# main.net
KiCad netlist of a schematic drawn in Altium Designer
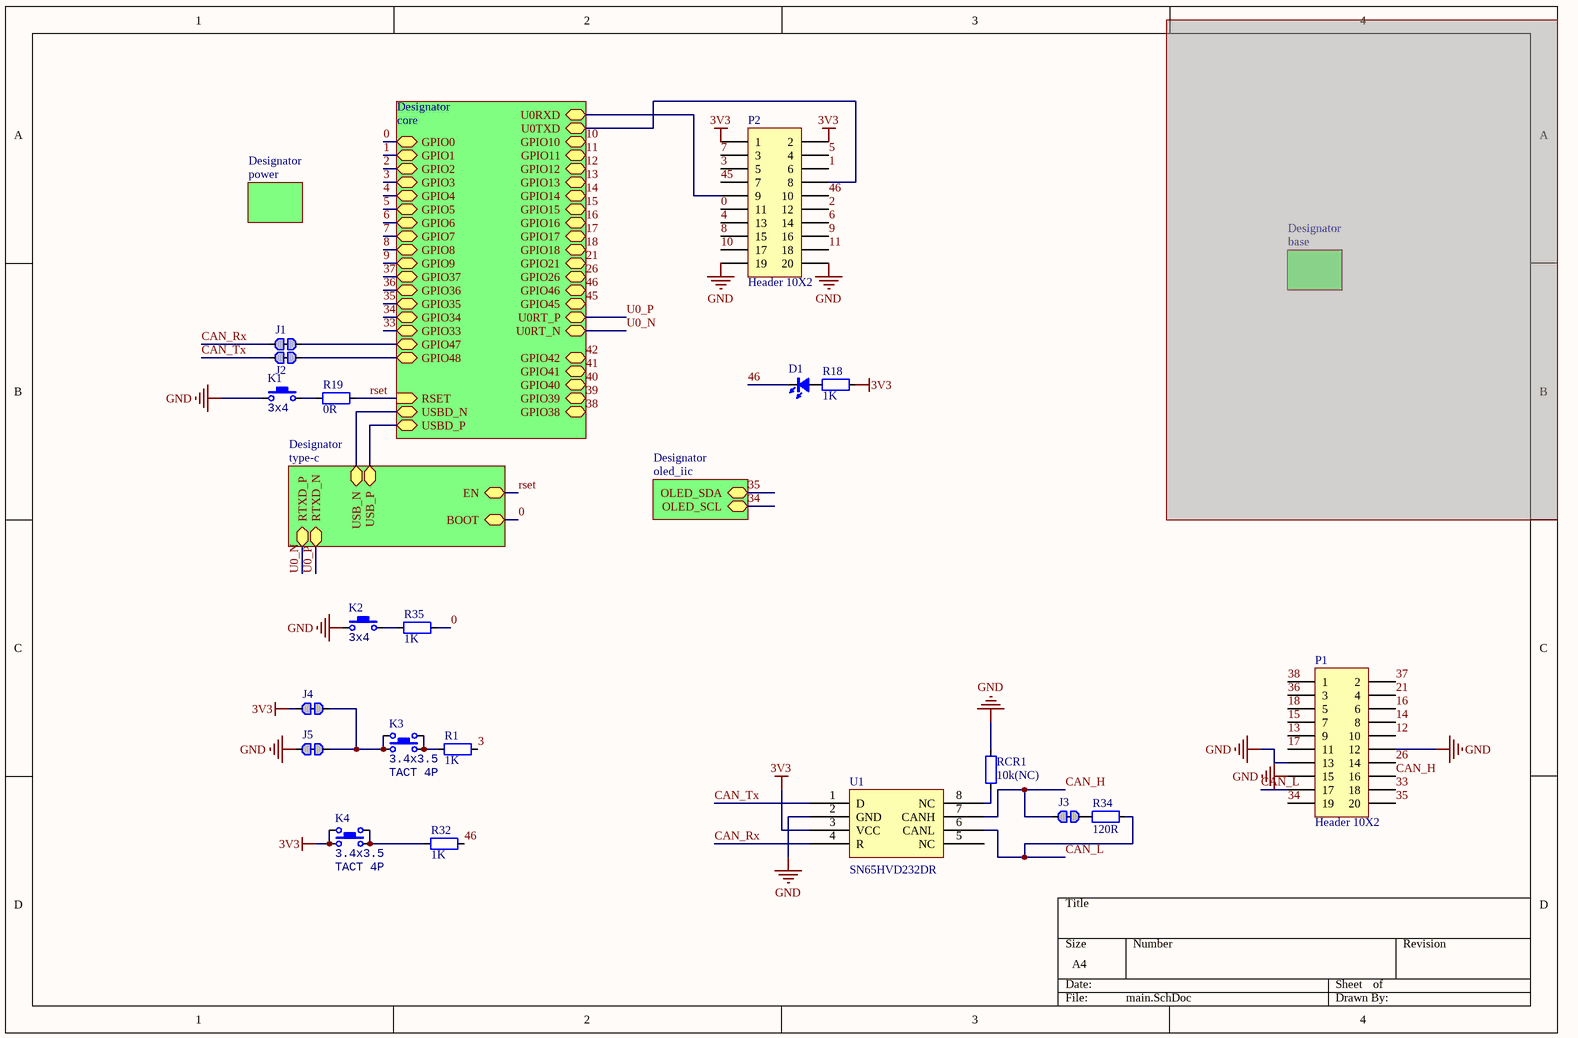
[diagram p0: main.SchDoc]

(export (version "E")
  (design (tool "Eeschema 10.0.6"))
  (components
    (comp (ref "D1")
      (value "color?")
      (footprint "LED_0402_RED")
      (description "LED")
      (libsource (lib "KitSprout") (part "LED_0402"))
    )
    (comp (ref "J1")
      (value "跳线")
      (footprint "0402-0R")
      (description "Resistor")
      (fields (field (name "PUBLISHER") "Altium Limited"))
      (libsource (lib "MyPcbLib") (part "跳线"))
    )
    (comp (ref "J2")
      (value "跳线")
      (footprint "0402-0R")
      (description "Resistor")
      (fields (field (name "PUBLISHER") "Altium Limited"))
      (libsource (lib "MyPcbLib") (part "跳线"))
    )
    (comp (ref "J3")
      (value "跳线")
      (footprint "0402-0R")
      (description "Resistor")
      (fields (field (name "PUBLISHER") "Altium Limited"))
      (libsource (lib "MyPcbLib") (part "跳线"))
    )
    (comp (ref "J4")
      (value "跳线")
      (footprint "0402-0R")
      (description "Resistor")
      (fields (field (name "PUBLISHER") "Altium Limited"))
      (libsource (lib "MyPcbLib") (part "跳线"))
    )
    (comp (ref "J5")
      (value "跳线")
      (footprint "0402-0R")
      (description "Resistor")
      (fields (field (name "PUBLISHER") "Altium Limited"))
      (libsource (lib "MyPcbLib") (part "跳线"))
    )
    (comp (ref "K1")
      (value "3x4")
      (footprint "ButtonTACT_3x4x2_180")
      (description "Button")
      (fields (field (name "Comment") "TACT 2P"))
      (libsource (lib "KitSprout") (part "ButtonTACT_3x4x2_180"))
    )
    (comp (ref "K2")
      (value "3x4")
      (footprint "ButtonTACT_3x4x2_180")
      (description "Button")
      (fields (field (name "Comment") "TACT 2P"))
      (libsource (lib "KitSprout") (part "ButtonTACT_3x4x2_180"))
    )
    (comp (ref "K3")
      (value "3.4x3.5")
      (footprint "ButtonTACT_3.5*3.55_90")
      (description "Button")
      (fields (field (name "TYPE") "TACT 4P") (field (name "Comment") "TACT 4P"))
      (libsource (lib "KitSprout") (part "ButtonTACT"))
    )
    (comp (ref "K4")
      (value "3.4x3.5")
      (footprint "ButtonTACT_3.5*3.55_90")
      (description "Button")
      (fields (field (name "TYPE") "TACT 4P") (field (name "Comment") "TACT 4P"))
      (libsource (lib "KitSprout") (part "ButtonTACT"))
    )
    (comp (ref "P1")
      (value "Header 10X2")
      (footprint "HEAER_0.8mm_2x10P_M")
      (description "Header, 10-Pin, Dual row")
      (fields (field (name "PUBLISHER") "Altium Limited"))
      (libsource (lib "Miscellaneous Connectors") (part "Header 10X2"))
    )
    (comp (ref "P2")
      (value "Header 10X2")
      (footprint "HEAER_0.8mm_2x10P_M")
      (description "Header, 10-Pin, Dual row")
      (fields (field (name "PUBLISHER") "Altium Limited"))
      (libsource (lib "Miscellaneous Connectors") (part "Header 10X2"))
    )
    (comp (ref "R1")
      (value "1K")
      (footprint "RES_0402")
      (description "Resistor")
      (libsource (lib "MyPcbLib") (part "电阻-0402"))
    )
    (comp (ref "R18")
      (value "1K")
      (footprint "RES_0402")
      (description "Resistor")
      (libsource (lib "") (part "电阻-0402_1"))
    )
    (comp (ref "R19")
      (value "0R")
      (footprint "RES_0402")
      (description "Resistor")
      (libsource (lib "MyPcbLib") (part "电阻-0402"))
    )
    (comp (ref "R32")
      (value "1K")
      (footprint "RES_0402")
      (description "Resistor")
      (libsource (lib "MyPcbLib") (part "电阻-0402"))
    )
    (comp (ref "R34")
      (value "120R")
      (footprint "RES_0402")
      (description "Resistor")
      (libsource (lib "MyPcbLib") (part "电阻-0402"))
    )
    (comp (ref "R35")
      (value "1K")
      (footprint "RES_0402")
      (description "Resistor")
      (libsource (lib "MyPcbLib") (part "电阻-0402"))
    )
    (comp (ref "RCR1")
      (value "10k(NC)")
      (footprint "RES_0402")
      (description "Resistor")
      (libsource (lib "") (part "电阻-0402_2"))
    )
    (comp (ref "U1")
      (value "SN65HVD232D")
      (footprint "SO-8")
      (fields
        (field (name "MANUFACTURER") "Texas Instruments")
        (field (name "MANUFACTURER PART NUMBER") "SN65HVD232DR")
      )
      (libsource (lib "MyPcbLib") (part "SN65HVD232D"))
    )
  )
  (nets
    (net (code "1") (name "/0") (class "Default")
      (node (ref "P2") (pin "11") (pinfunction "11_11") (pintype "passive"))
      (node (ref "R35") (pin "2") (pinfunction "2_2") (pintype "passive"))
    )
    (net (code "2") (name "/1") (class "Default")
      (node (ref "P2") (pin "6") (pinfunction "6_6") (pintype "passive"))
    )
    (net (code "3") (name "/2") (class "Default")
      (node (ref "P2") (pin "12") (pinfunction "12_12") (pintype "passive"))
    )
    (net (code "4") (name "/3") (class "Default")
      (node (ref "P2") (pin "5") (pinfunction "5_5") (pintype "passive"))
      (node (ref "R1") (pin "2") (pinfunction "2_2") (pintype "passive"))
    )
    (net (code "5") (name "/4") (class "Default")
      (node (ref "P2") (pin "13") (pinfunction "13_13") (pintype "passive"))
    )
    (net (code "6") (name "/5") (class "Default")
      (node (ref "P2") (pin "4") (pinfunction "4_4") (pintype "passive"))
    )
    (net (code "7") (name "/6") (class "Default")
      (node (ref "P2") (pin "14") (pinfunction "14_14") (pintype "passive"))
    )
    (net (code "8") (name "/7") (class "Default")
      (node (ref "P2") (pin "3") (pinfunction "3_3") (pintype "passive"))
    )
    (net (code "9") (name "/8") (class "Default")
      (node (ref "P2") (pin "15") (pinfunction "15_15") (pintype "passive"))
    )
    (net (code "10") (name "/9") (class "Default")
      (node (ref "P2") (pin "16") (pinfunction "16_16") (pintype "passive"))
    )
    (net (code "11") (name "/10") (class "Default")
      (node (ref "P2") (pin "17") (pinfunction "17_17") (pintype "passive"))
    )
    (net (code "12") (name "/11") (class "Default")
      (node (ref "P2") (pin "18") (pinfunction "18_18") (pintype "passive"))
    )
    (net (code "13") (name "/12") (class "Default")
      (node (ref "P1") (pin "10") (pinfunction "10_10") (pintype "passive"))
    )
    (net (code "14") (name "/13") (class "Default")
      (node (ref "P1") (pin "9") (pinfunction "9_9") (pintype "passive"))
    )
    (net (code "15") (name "/14") (class "Default")
      (node (ref "P1") (pin "8") (pinfunction "8_8") (pintype "passive"))
    )
    (net (code "16") (name "/15") (class "Default")
      (node (ref "P1") (pin "7") (pinfunction "7_7") (pintype "passive"))
    )
    (net (code "17") (name "/16") (class "Default")
      (node (ref "P1") (pin "6") (pinfunction "6_6") (pintype "passive"))
    )
    (net (code "18") (name "/17") (class "Default")
      (node (ref "P1") (pin "11") (pinfunction "11_11") (pintype "passive"))
    )
    (net (code "19") (name "/18") (class "Default")
      (node (ref "P1") (pin "5") (pinfunction "5_5") (pintype "passive"))
    )
    (net (code "20") (name "/21") (class "Default")
      (node (ref "P1") (pin "4") (pinfunction "4_4") (pintype "passive"))
    )
    (net (code "21") (name "/26") (class "Default")
      (node (ref "P1") (pin "14") (pinfunction "14_14") (pintype "passive"))
    )
    (net (code "22") (name "/33") (class "Default")
      (node (ref "P1") (pin "18") (pinfunction "18_18") (pintype "passive"))
    )
    (net (code "23") (name "/34") (class "Default")
      (node (ref "P1") (pin "19") (pinfunction "19_19") (pintype "passive"))
    )
    (net (code "24") (name "/35") (class "Default")
      (node (ref "P1") (pin "20") (pinfunction "20_20") (pintype "passive"))
    )
    (net (code "25") (name "/36") (class "Default")
      (node (ref "P1") (pin "3") (pinfunction "3_3") (pintype "passive"))
    )
    (net (code "26") (name "/37") (class "Default")
      (node (ref "P1") (pin "2") (pinfunction "2_2") (pintype "passive"))
    )
    (net (code "27") (name "/38") (class "Default")
      (node (ref "P1") (pin "1") (pinfunction "1_1") (pintype "passive"))
    )
    (net (code "32") (name "/45") (class "Default")
      (node (ref "P2") (pin "7") (pinfunction "7_7") (pintype "passive"))
    )
    (net (code "33") (name "/46") (class "Default")
      (node (ref "D1") (pin "2") (pinfunction "K_2") (pintype "passive"))
      (node (ref "P2") (pin "10") (pinfunction "10_10") (pintype "passive"))
      (node (ref "R32") (pin "2") (pinfunction "2_2") (pintype "passive"))
    )
    (net (code "34") (name "/CAN_H") (class "Default")
      (node (ref "J3") (pin "1") (pinfunction "1_1") (pintype "passive"))
      (node (ref "P1") (pin "16") (pinfunction "16_16") (pintype "passive"))
      (node (ref "U1") (pin "7") (pinfunction "CANH_7") (pintype "passive"))
    )
    (net (code "35") (name "/CAN_L") (class "Default")
      (node (ref "P1") (pin "17") (pinfunction "17_17") (pintype "passive"))
      (node (ref "R34") (pin "2") (pinfunction "2_2") (pintype "passive"))
      (node (ref "U1") (pin "6") (pinfunction "CANL_6") (pintype "passive"))
    )
    (net (code "36") (name "/CAN_Rx") (class "Default")
      (node (ref "J1") (pin "1") (pinfunction "1_1") (pintype "passive"))
      (node (ref "U1") (pin "4") (pinfunction "R_4") (pintype "passive"))
    )
    (net (code "37") (name "/CAN_Tx") (class "Default")
      (node (ref "J2") (pin "1") (pinfunction "1_1") (pintype "passive"))
      (node (ref "U1") (pin "1") (pinfunction "D_1") (pintype "passive"))
    )
    (net (code "38") (name "/GPIO47") (class "Default")
      (node (ref "J1") (pin "2") (pinfunction "2_2") (pintype "passive"))
    )
    (net (code "39") (name "/GPIO48") (class "Default")
      (node (ref "J2") (pin "2") (pinfunction "2_2") (pintype "passive"))
    )
    (net (code "40") (name "/U0RXD") (class "Default")
      (node (ref "P2") (pin "9") (pinfunction "9_9") (pintype "passive"))
    )
    (net (code "41") (name "/U0TXD") (class "Default")
      (node (ref "P2") (pin "8") (pinfunction "8_8") (pintype "passive"))
    )
    (net (code "46") (name "/rset") (class "Default")
      (node (ref "R19") (pin "2") (pinfunction "2_2") (pintype "passive"))
    )
    (net (code "47") (name "3V3") (class "Default")
      (node (ref "J4") (pin "1") (pinfunction "1_1") (pintype "passive"))
      (node (ref "K4") (pin "1") (pinfunction "1_1") (pintype "passive"))
      (node (ref "K4") (pin "3") (pinfunction "3_3") (pintype "passive"))
      (node (ref "P2") (pin "1") (pinfunction "1_1") (pintype "passive"))
      (node (ref "P2") (pin "2") (pinfunction "2_2") (pintype "passive"))
      (node (ref "R18") (pin "1") (pinfunction "1_1") (pintype "passive"))
      (node (ref "U1") (pin "3") (pinfunction "VCC_3") (pintype "passive"))
    )
    (net (code "48") (name "GND") (class "Default")
      (node (ref "J5") (pin "1") (pinfunction "1_1") (pintype "passive"))
      (node (ref "K1") (pin "1") (pinfunction "1_1") (pintype "passive"))
      (node (ref "K2") (pin "1") (pinfunction "1_1") (pintype "passive"))
      (node (ref "P1") (pin "12") (pinfunction "12_12") (pintype "passive"))
      (node (ref "P1") (pin "13") (pinfunction "13_13") (pintype "passive"))
      (node (ref "P1") (pin "15") (pinfunction "15_15") (pintype "passive"))
      (node (ref "P2") (pin "19") (pinfunction "19_19") (pintype "passive"))
      (node (ref "P2") (pin "20") (pinfunction "20_20") (pintype "passive"))
      (node (ref "RCR1") (pin "2") (pinfunction "2_2") (pintype "passive"))
      (node (ref "U1") (pin "2") (pinfunction "GND_2") (pintype "passive"))
    )
    (net (code "49") (name "Net-(D1-A)") (class "Default")
      (node (ref "D1") (pin "1") (pinfunction "A_1") (pintype "passive"))
      (node (ref "R18") (pin "2") (pinfunction "2_2") (pintype "passive"))
    )
    (net (code "50") (name "Net-(J3-Pad2)") (class "Default")
      (node (ref "J3") (pin "2") (pinfunction "2_2") (pintype "passive"))
      (node (ref "R34") (pin "1") (pinfunction "1_1") (pintype "passive"))
    )
    (net (code "51") (name "Net-(J4-Pad2)") (class "Default")
      (node (ref "J4") (pin "2") (pinfunction "2_2") (pintype "passive"))
      (node (ref "J5") (pin "2") (pinfunction "2_2") (pintype "passive"))
      (node (ref "K3") (pin "1") (pinfunction "1_1") (pintype "passive"))
      (node (ref "K3") (pin "3") (pinfunction "3_3") (pintype "passive"))
    )
    (net (code "52") (name "Net-(K1-Pad2)") (class "Default")
      (node (ref "K1") (pin "2") (pinfunction "2_2") (pintype "passive"))
      (node (ref "R19") (pin "1") (pinfunction "1_1") (pintype "passive"))
    )
    (net (code "53") (name "Net-(K2-Pad2)") (class "Default")
      (node (ref "K2") (pin "2") (pinfunction "2_2") (pintype "passive"))
      (node (ref "R35") (pin "1") (pinfunction "1_1") (pintype "passive"))
    )
    (net (code "54") (name "Net-(K3-Pad2)") (class "Default")
      (node (ref "K3") (pin "2") (pinfunction "2_2") (pintype "passive"))
      (node (ref "K3") (pin "4") (pinfunction "4_4") (pintype "passive"))
      (node (ref "R1") (pin "1") (pinfunction "1_1") (pintype "passive"))
    )
    (net (code "55") (name "Net-(K4-Pad2)") (class "Default")
      (node (ref "K4") (pin "2") (pinfunction "2_2") (pintype "passive"))
      (node (ref "K4") (pin "4") (pinfunction "4_4") (pintype "passive"))
      (node (ref "R32") (pin "1") (pinfunction "1_1") (pintype "passive"))
    )
    (net (code "56") (name "Net-(RCR1-Pad1)") (class "Default")
      (node (ref "RCR1") (pin "1") (pinfunction "1_1") (pintype "passive"))
      (node (ref "U1") (pin "8") (pinfunction "NC_8") (pintype "passive"))
    )
    (net (code "57") (name "unconnected-(U1-NC-Pad5)") (class "Default")
      (node (ref "U1") (pin "5") (pinfunction "NC_5") (pintype "passive"))
    )
  )
)
